# accra_A.net
KiCad netlist of a schematic drawn in EAGLE
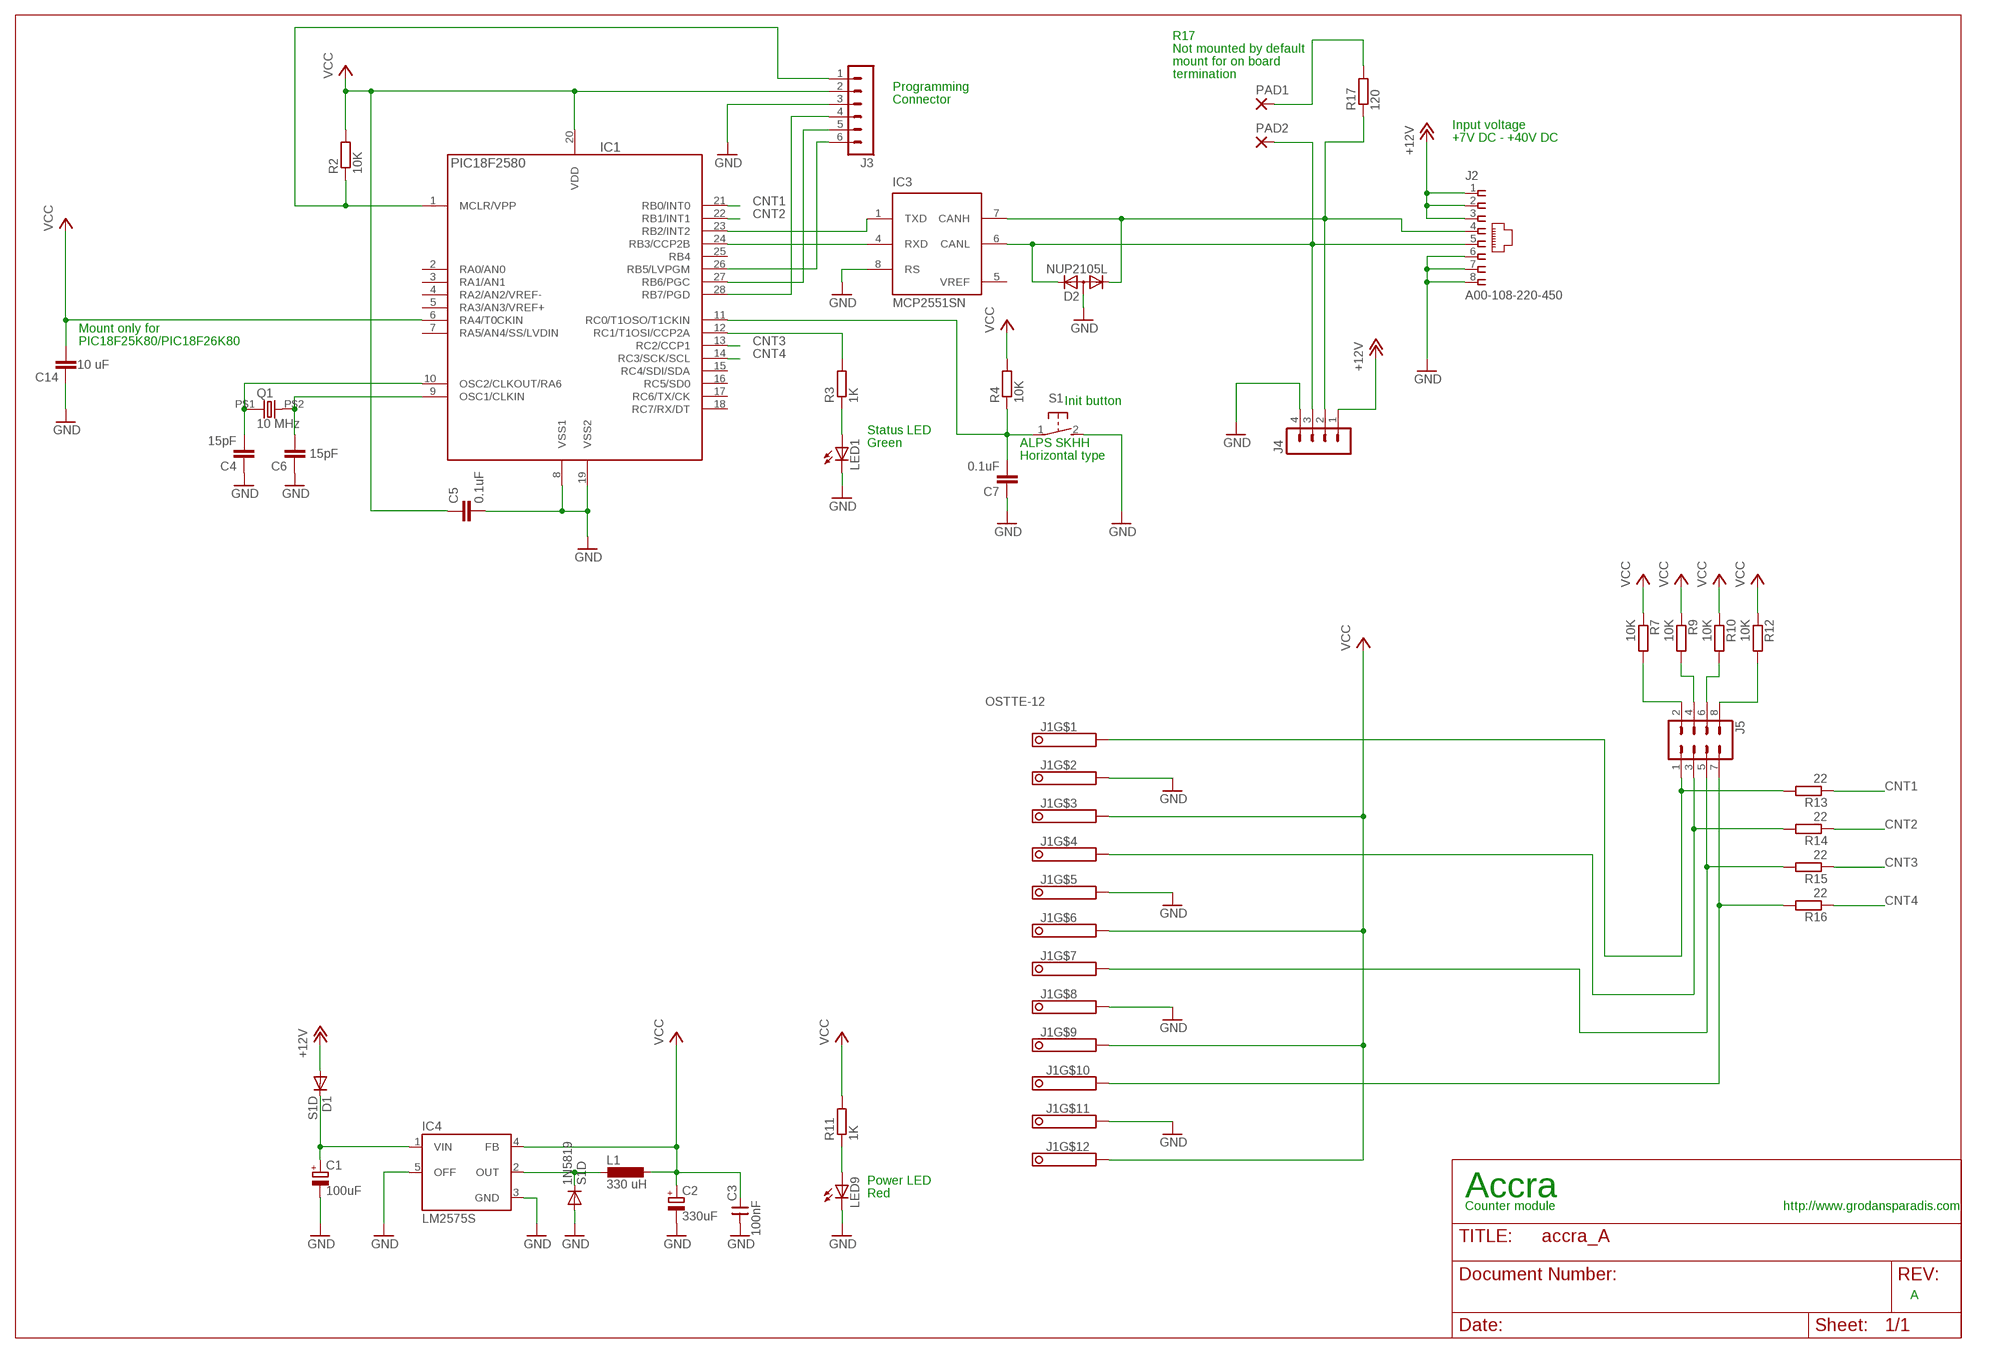
[diagram p0: schematic, sheet 1]

(export (version "E")
  (design (tool "Eeschema 10.0.6"))
  (components
    (comp (ref "1N5819")
      (value "S1D")
      (footprint "eagle-import:SOD123")
      (libsource (lib "eagle-import") (part "DIODE-SOD123"))
    )
    (comp (ref "C1")
      (value "100uF")
      (footprint "eagle-import:PANASONIC_D")
      (libsource (lib "eagle-import") (part "CPOL-EUD"))
    )
    (comp (ref "C2")
      (value "330uF")
      (footprint "eagle-import:PANASONIC_D")
      (libsource (lib "eagle-import") (part "CPOL-EUD"))
    )
    (comp (ref "C3")
      (value "100nF")
      (footprint "eagle-import:0805")
      (libsource (lib "eagle-import") (part "CNP-0805"))
    )
    (comp (ref "C4")
      (value "15pF")
      (footprint "eagle-import:C0805")
      (libsource (lib "eagle-import") (part "C-EUC0805"))
    )
    (comp (ref "C5")
      (value "0.1uF")
      (footprint "eagle-import:C0805")
      (libsource (lib "eagle-import") (part "C-EUC0805"))
    )
    (comp (ref "C6")
      (value "15pF")
      (footprint "eagle-import:C0805")
      (libsource (lib "eagle-import") (part "C-EUC0805"))
    )
    (comp (ref "C7")
      (value "0.1uF")
      (footprint "eagle-import:C0805")
      (libsource (lib "eagle-import") (part "C-EUC0805"))
    )
    (comp (ref "C14")
      (value "10 uF")
      (footprint "eagle-import:C0805")
      (libsource (lib "eagle-import") (part "C-EUC0805"))
    )
    (comp (ref "D1")
      (value "S1D")
      (footprint "eagle-import:SOD123")
      (libsource (lib "eagle-import") (part "DIODE-SOD123"))
    )
    (comp (ref "D2")
      (value "NUP2105L")
      (footprint "eagle-import:SOT23")
      (libsource (lib "eagle-import") (part "DIODE-2CA|ACSOT23"))
    )
    (comp (ref "IC1")
      (value "PIC18F2580")
      (footprint "eagle-import:SO28")
      (libsource (lib "eagle-import") (part "PIC18F252-?I/SOL"))
    )
    (comp (ref "IC3")
      (value "MCP2551SN")
      (footprint "eagle-import:SO-08")
      (libsource (lib "eagle-import") (part "MCP2551SN"))
    )
    (comp (ref "IC4")
      (value "LM2575S")
      (footprint "eagle-import:TO263-5")
      (libsource (lib "eagle-import") (part "LM2575S"))
    )
    (comp (ref "J1")
      (value "OSTTE-12")
      (footprint "eagle-import:PINHEAD-12")
      (libsource (lib "eagle-import") (part "OSTTE-12"))
    )
    (comp (ref "J2")
      (value "A00-108-220-450")
      (footprint "eagle-import:RJ-45")
      (libsource (lib "eagle-import") (part "A00-108-220-450"))
    )
    (comp (ref "J3")
      (value "MA06-1")
      (footprint "eagle-import:MA06-1")
      (libsource (lib "eagle-import") (part "MA06-1"))
    )
    (comp (ref "J4")
      (value "MA04-1")
      (footprint "eagle-import:MA04-1")
      (libsource (lib "eagle-import") (part "MA04-1"))
    )
    (comp (ref "J5")
      (value "MA04-2")
      (footprint "eagle-import:MA04-2")
      (libsource (lib "eagle-import") (part "MA04-2"))
    )
    (comp (ref "L1")
      (value "330 uH")
      (footprint "eagle-import:DO3316P")
      (libsource (lib "eagle-import") (part "DO3316P"))
    )
    (comp (ref "LED1")
      (value "LEDCHIP-LED0805")
      (footprint "eagle-import:CHIP-LED0805")
      (libsource (lib "eagle-import") (part "LEDCHIP-LED0805"))
    )
    (comp (ref "LED9")
      (value "LEDCHIP-LED0805")
      (footprint "eagle-import:CHIP-LED0805")
      (libsource (lib "eagle-import") (part "LEDCHIP-LED0805"))
    )
    (comp (ref "PAD1")
      (value "1,6/0,8")
      (footprint "eagle-import:1,6_0,8")
      (libsource (lib "eagle-import") (part "1,6/0,8"))
    )
    (comp (ref "PAD2")
      (value "1,6/0,8")
      (footprint "eagle-import:1,6_0,8")
      (libsource (lib "eagle-import") (part "1,6/0,8"))
    )
    (comp (ref "Q1")
      (value "10 MHz")
      (footprint "eagle-import:9C")
      (libsource (lib "eagle-import") (part "HC-49S"))
    )
    (comp (ref "R2")
      (value "10K")
      (footprint "eagle-import:R0805")
      (libsource (lib "eagle-import") (part "R-EU_R0805"))
    )
    (comp (ref "R3")
      (value "1K")
      (footprint "eagle-import:R0805")
      (libsource (lib "eagle-import") (part "R-EU_R0805"))
    )
    (comp (ref "R4")
      (value "10K")
      (footprint "eagle-import:R0805")
      (libsource (lib "eagle-import") (part "R-EU_R0805"))
    )
    (comp (ref "R7")
      (value "10K")
      (footprint "eagle-import:R0805")
      (libsource (lib "eagle-import") (part "R-EU_R0805"))
    )
    (comp (ref "R9")
      (value "10K")
      (footprint "eagle-import:R0805")
      (libsource (lib "eagle-import") (part "R-EU_R0805"))
    )
    (comp (ref "R10")
      (value "10K")
      (footprint "eagle-import:R0805")
      (libsource (lib "eagle-import") (part "R-EU_R0805"))
    )
    (comp (ref "R11")
      (value "1K")
      (footprint "eagle-import:R0805")
      (libsource (lib "eagle-import") (part "R-EU_R0805"))
    )
    (comp (ref "R12")
      (value "10K")
      (footprint "eagle-import:R0805")
      (libsource (lib "eagle-import") (part "R-EU_R0805"))
    )
    (comp (ref "R13")
      (value "22")
      (footprint "eagle-import:R0805")
      (libsource (lib "eagle-import") (part "R-EU_R0805"))
    )
    (comp (ref "R14")
      (value "22")
      (footprint "eagle-import:R0805")
      (libsource (lib "eagle-import") (part "R-EU_R0805"))
    )
    (comp (ref "R15")
      (value "22")
      (footprint "eagle-import:R0805")
      (libsource (lib "eagle-import") (part "R-EU_R0805"))
    )
    (comp (ref "R16")
      (value "22")
      (footprint "eagle-import:R0805")
      (libsource (lib "eagle-import") (part "R-EU_R0805"))
    )
    (comp (ref "R17")
      (value "120")
      (footprint "eagle-import:R0805")
      (libsource (lib "eagle-import") (part "R-EU_R0805"))
    )
    (comp (ref "S1")
      (value "31-XX")
      (footprint "eagle-import:B3F-31XX")
      (fields (field (name "MPN") "B3F-3100"))
      (libsource (lib "eagle-import") (part "31-XX"))
    )
  )
  (nets
    (net (code "1") (name "+12V") (class "Default")
      (node (ref "D1") (pin "A") (pinfunction "A_A") (pintype "passive"))
      (node (ref "J2") (pin "1") (pinfunction "1_1") (pintype "passive"))
      (node (ref "J2") (pin "2") (pinfunction "2_2") (pintype "passive"))
      (node (ref "J2") (pin "3") (pinfunction "3_3") (pintype "passive"))
      (node (ref "J4") (pin "1") (pinfunction "1_1") (pintype "passive"))
    )
    (net (code "2") (name "/CNT1") (class "Default")
      (node (ref "IC1") (pin "21") (pinfunction "RB0/INT0_21") (pintype "bidirectional"))
      (node (ref "R13") (pin "1") (pinfunction "1_1") (pintype "passive"))
    )
    (net (code "3") (name "/CNT2") (class "Default")
      (node (ref "IC1") (pin "22") (pinfunction "RB1/INT1_22") (pintype "bidirectional"))
      (node (ref "R14") (pin "1") (pinfunction "1_1") (pintype "passive"))
    )
    (net (code "4") (name "/CNT3") (class "Default")
      (node (ref "IC1") (pin "13") (pinfunction "RC2/CCP1_13") (pintype "bidirectional"))
      (node (ref "R15") (pin "1") (pinfunction "1_1") (pintype "passive"))
    )
    (net (code "5") (name "/CNT4") (class "Default")
      (node (ref "IC1") (pin "14") (pinfunction "RC3/SCK/SCL_14") (pintype "bidirectional"))
      (node (ref "R16") (pin "1") (pinfunction "1_1") (pintype "passive"))
    )
    (net (code "6") (name "/VREF") (class "Default")
      (node (ref "IC3") (pin "5") (pinfunction "VREF_5") (pintype "power_in"))
    )
    (net (code "7") (name "GND") (class "Default")
      (node (ref "1N5819") (pin "A") (pinfunction "A_A") (pintype "passive"))
      (node (ref "C1") (pin "-") (pinfunction "-_-") (pintype "passive"))
      (node (ref "C14") (pin "1") (pinfunction "1_1") (pintype "passive"))
      (node (ref "C2") (pin "-") (pinfunction "-_-") (pintype "passive"))
      (node (ref "C3") (pin "1") (pinfunction "1_1") (pintype "passive"))
      (node (ref "C4") (pin "1") (pinfunction "1_1") (pintype "passive"))
      (node (ref "C5") (pin "2") (pinfunction "2_2") (pintype "passive"))
      (node (ref "C6") (pin "1") (pinfunction "1_1") (pintype "passive"))
      (node (ref "C7") (pin "1") (pinfunction "1_1") (pintype "passive"))
      (node (ref "D2") (pin "3") (pinfunction "A_3") (pintype "passive"))
      (node (ref "IC1") (pin "19") (pinfunction "VSS2_19") (pintype "power_in"))
      (node (ref "IC1") (pin "8") (pinfunction "VSS1_8") (pintype "power_in"))
      (node (ref "IC3") (pin "8") (pinfunction "RS_8") (pintype "input"))
      (node (ref "IC4") (pin "3") (pinfunction "GND_3") (pintype "power_in"))
      (node (ref "IC4") (pin "5") (pinfunction "OFF_5") (pintype "input"))
      (node (ref "J1") (pin "11") (pinfunction "K_11") (pintype "passive"))
      (node (ref "J1") (pin "2") (pinfunction "K_2") (pintype "passive"))
      (node (ref "J1") (pin "5") (pinfunction "K_5") (pintype "passive"))
      (node (ref "J1") (pin "8") (pinfunction "K_8") (pintype "passive"))
      (node (ref "J2") (pin "6") (pinfunction "6_6") (pintype "passive"))
      (node (ref "J2") (pin "7") (pinfunction "7_7") (pintype "passive"))
      (node (ref "J2") (pin "8") (pinfunction "8_8") (pintype "passive"))
      (node (ref "J3") (pin "3") (pinfunction "3_3") (pintype "passive"))
      (node (ref "J4") (pin "4") (pinfunction "4_4") (pintype "passive"))
      (node (ref "LED1") (pin "C") (pinfunction "C_C") (pintype "passive"))
      (node (ref "LED9") (pin "C") (pinfunction "C_C") (pintype "passive"))
      (node (ref "S1") (pin "2") (pinfunction "S_2") (pintype "passive"))
    )
    (net (code "8") (name "Net-(D2-K1)") (class "Default")
      (node (ref "D2") (pin "1") (pinfunction "K1_1") (pintype "passive"))
      (node (ref "IC3") (pin "7") (pinfunction "CANH_7") (pintype "bidirectional"))
      (node (ref "J2") (pin "4") (pinfunction "4_4") (pintype "passive"))
      (node (ref "J4") (pin "2") (pinfunction "2_2") (pintype "passive"))
      (node (ref "R17") (pin "1") (pinfunction "1_1") (pintype "passive"))
    )
    (net (code "9") (name "Net-(D2-K2)") (class "Default")
      (node (ref "D2") (pin "2") (pinfunction "K2_2") (pintype "passive"))
      (node (ref "IC3") (pin "6") (pinfunction "CANL_6") (pintype "bidirectional"))
      (node (ref "J2") (pin "5") (pinfunction "5_5") (pintype "passive"))
      (node (ref "J4") (pin "3") (pinfunction "3_3") (pintype "passive"))
      (node (ref "PAD2") (pin "1") (pinfunction "P_1") (pintype "passive"))
    )
    (net (code "10") (name "Net-(IC1-MCLR{slash}VPP)") (class "Default")
      (node (ref "IC1") (pin "1") (pinfunction "MCLR/VPP_1") (pintype "input"))
      (node (ref "J3") (pin "1") (pinfunction "1_1") (pintype "passive"))
      (node (ref "R2") (pin "1") (pinfunction "1_1") (pintype "passive"))
    )
    (net (code "11") (name "Net-(IC1-OSC1{slash}CLKIN)") (class "Default")
      (node (ref "C6") (pin "2") (pinfunction "2_2") (pintype "passive"))
      (node (ref "IC1") (pin "9") (pinfunction "OSC1/CLKIN_9") (pintype "input"))
      (node (ref "Q1") (pin "P$2") (pinfunction "2_P$2") (pintype "passive"))
    )
    (net (code "12") (name "Net-(IC1-OSC2{slash}CLKOUT{slash}RA6)") (class "Default")
      (node (ref "C4") (pin "2") (pinfunction "2_2") (pintype "passive"))
      (node (ref "IC1") (pin "10") (pinfunction "OSC2/CLKOUT/RA6_10") (pintype "output"))
      (node (ref "Q1") (pin "P$1") (pinfunction "1_P$1") (pintype "passive"))
    )
    (net (code "13") (name "Net-(IC1-RB2{slash}INT2)") (class "Default")
      (node (ref "IC1") (pin "23") (pinfunction "RB2/INT2_23") (pintype "bidirectional"))
      (node (ref "IC3") (pin "1") (pinfunction "TXD_1") (pintype "input"))
    )
    (net (code "14") (name "Net-(IC1-RB3{slash}CCP2B)") (class "Default")
      (node (ref "IC1") (pin "24") (pinfunction "RB3/CCP2B_24") (pintype "bidirectional"))
      (node (ref "IC3") (pin "4") (pinfunction "RXD_4") (pintype "output"))
    )
    (net (code "15") (name "Net-(IC1-RB5{slash}LVPGM)") (class "Default")
      (node (ref "IC1") (pin "26") (pinfunction "RB5/LVPGM_26") (pintype "bidirectional"))
      (node (ref "J3") (pin "6") (pinfunction "6_6") (pintype "passive"))
    )
    (net (code "16") (name "Net-(IC1-RB6{slash}PGC)") (class "Default")
      (node (ref "IC1") (pin "27") (pinfunction "RB6/PGC_27") (pintype "bidirectional"))
      (node (ref "J3") (pin "5") (pinfunction "5_5") (pintype "passive"))
    )
    (net (code "17") (name "Net-(IC1-RB7{slash}PGD)") (class "Default")
      (node (ref "IC1") (pin "28") (pinfunction "RB7/PGD_28") (pintype "bidirectional"))
      (node (ref "J3") (pin "4") (pinfunction "4_4") (pintype "passive"))
    )
    (net (code "18") (name "Net-(IC1-RC0{slash}T1OSO{slash}T1CKIN)") (class "Default")
      (node (ref "C7") (pin "2") (pinfunction "2_2") (pintype "passive"))
      (node (ref "IC1") (pin "11") (pinfunction "RC0/T1OSO/T1CKIN_11") (pintype "bidirectional"))
      (node (ref "R4") (pin "1") (pinfunction "1_1") (pintype "passive"))
      (node (ref "S1") (pin "1") (pinfunction "P_1") (pintype "passive"))
    )
    (net (code "19") (name "Net-(IC1-RC1{slash}T1OSI{slash}CCP2A)") (class "Default")
      (node (ref "IC1") (pin "12") (pinfunction "RC1/T1OSI/CCP2A_12") (pintype "bidirectional"))
      (node (ref "R3") (pin "2") (pinfunction "2_2") (pintype "passive"))
    )
    (net (code "20") (name "Net-(IC4-OUT)") (class "Default")
      (node (ref "1N5819") (pin "C") (pinfunction "C_C") (pintype "passive"))
      (node (ref "IC4") (pin "2") (pinfunction "OUT_2") (pintype "output"))
      (node (ref "L1") (pin "1") (pinfunction "1_1") (pintype "passive"))
    )
    (net (code "21") (name "Net-(IC4-VIN)") (class "Default")
      (node (ref "C1") (pin "+") (pinfunction "+_+") (pintype "passive"))
      (node (ref "D1") (pin "C") (pinfunction "C_C") (pintype "passive"))
      (node (ref "IC4") (pin "1") (pinfunction "VIN_1") (pintype "power_in"))
    )
    (net (code "22") (name "Net-(J1A-K)") (class "Default")
      (node (ref "J1") (pin "1") (pinfunction "K_1") (pintype "passive"))
      (node (ref "J5") (pin "1") (pinfunction "1_1") (pintype "passive"))
      (node (ref "R13") (pin "2") (pinfunction "2_2") (pintype "passive"))
    )
    (net (code "23") (name "Net-(J1B-K)") (class "Default")
      (node (ref "J1") (pin "10") (pinfunction "K_10") (pintype "passive"))
      (node (ref "J5") (pin "7") (pinfunction "7_7") (pintype "passive"))
      (node (ref "R16") (pin "2") (pinfunction "2_2") (pintype "passive"))
    )
    (net (code "24") (name "Net-(J1G-K)") (class "Default")
      (node (ref "J1") (pin "4") (pinfunction "K_4") (pintype "passive"))
      (node (ref "J5") (pin "3") (pinfunction "3_3") (pintype "passive"))
      (node (ref "R14") (pin "2") (pinfunction "2_2") (pintype "passive"))
    )
    (net (code "25") (name "Net-(J1J-K)") (class "Default")
      (node (ref "J1") (pin "7") (pinfunction "K_7") (pintype "passive"))
      (node (ref "J5") (pin "5") (pinfunction "5_5") (pintype "passive"))
      (node (ref "R15") (pin "2") (pinfunction "2_2") (pintype "passive"))
    )
    (net (code "26") (name "Net-(J5-Pad2)") (class "Default")
      (node (ref "J5") (pin "2") (pinfunction "2_2") (pintype "passive"))
      (node (ref "R7") (pin "2") (pinfunction "2_2") (pintype "passive"))
    )
    (net (code "27") (name "Net-(J5-Pad4)") (class "Default")
      (node (ref "J5") (pin "4") (pinfunction "4_4") (pintype "passive"))
      (node (ref "R9") (pin "2") (pinfunction "2_2") (pintype "passive"))
    )
    (net (code "28") (name "Net-(J5-Pad6)") (class "Default")
      (node (ref "J5") (pin "6") (pinfunction "6_6") (pintype "passive"))
      (node (ref "R10") (pin "2") (pinfunction "2_2") (pintype "passive"))
    )
    (net (code "29") (name "Net-(J5-Pad8)") (class "Default")
      (node (ref "J5") (pin "8") (pinfunction "8_8") (pintype "passive"))
      (node (ref "R12") (pin "2") (pinfunction "2_2") (pintype "passive"))
    )
    (net (code "30") (name "Net-(LED1-PadA)") (class "Default")
      (node (ref "LED1") (pin "A") (pinfunction "A_A") (pintype "passive"))
      (node (ref "R3") (pin "1") (pinfunction "1_1") (pintype "passive"))
    )
    (net (code "31") (name "Net-(LED9-PadA)") (class "Default")
      (node (ref "LED9") (pin "A") (pinfunction "A_A") (pintype "passive"))
      (node (ref "R11") (pin "1") (pinfunction "1_1") (pintype "passive"))
    )
    (net (code "32") (name "Net-(PAD1-P)") (class "Default")
      (node (ref "PAD1") (pin "1") (pinfunction "P_1") (pintype "passive"))
      (node (ref "R17") (pin "2") (pinfunction "2_2") (pintype "passive"))
    )
    (net (code "33") (name "VCC") (class "Default")
      (node (ref "C14") (pin "2") (pinfunction "2_2") (pintype "passive"))
      (node (ref "C2") (pin "+") (pinfunction "+_+") (pintype "passive"))
      (node (ref "C3") (pin "2") (pinfunction "2_2") (pintype "passive"))
      (node (ref "C5") (pin "1") (pinfunction "1_1") (pintype "passive"))
      (node (ref "IC1") (pin "20") (pinfunction "VDD_20") (pintype "power_in"))
      (node (ref "IC1") (pin "6") (pinfunction "RA4/T0CKIN_6") (pintype "open_collector"))
      (node (ref "IC4") (pin "4") (pinfunction "FB_4") (pintype "input"))
      (node (ref "J1") (pin "12") (pinfunction "K_12") (pintype "passive"))
      (node (ref "J1") (pin "3") (pinfunction "K_3") (pintype "passive"))
      (node (ref "J1") (pin "6") (pinfunction "K_6") (pintype "passive"))
      (node (ref "J1") (pin "9") (pinfunction "K_9") (pintype "passive"))
      (node (ref "J3") (pin "2") (pinfunction "2_2") (pintype "passive"))
      (node (ref "L1") (pin "2") (pinfunction "2_2") (pintype "passive"))
      (node (ref "R10") (pin "1") (pinfunction "1_1") (pintype "passive"))
      (node (ref "R11") (pin "2") (pinfunction "2_2") (pintype "passive"))
      (node (ref "R12") (pin "1") (pinfunction "1_1") (pintype "passive"))
      (node (ref "R2") (pin "2") (pinfunction "2_2") (pintype "passive"))
      (node (ref "R4") (pin "2") (pinfunction "2_2") (pintype "passive"))
      (node (ref "R7") (pin "1") (pinfunction "1_1") (pintype "passive"))
      (node (ref "R9") (pin "1") (pinfunction "1_1") (pintype "passive"))
    )
    (net (code "34") (name "unconnected-(IC1-RA0{slash}AN0-Pad2)") (class "Default")
      (node (ref "IC1") (pin "2") (pinfunction "RA0/AN0_2") (pintype "bidirectional"))
    )
    (net (code "35") (name "unconnected-(IC1-RA1{slash}AN1-Pad3)") (class "Default")
      (node (ref "IC1") (pin "3") (pinfunction "RA1/AN1_3") (pintype "bidirectional"))
    )
    (net (code "36") (name "unconnected-(IC1-RA2{slash}AN2{slash}VREF--Pad4)") (class "Default")
      (node (ref "IC1") (pin "4") (pinfunction "RA2/AN2/VREF-_4") (pintype "bidirectional"))
    )
    (net (code "37") (name "unconnected-(IC1-RA3{slash}AN3{slash}VREF+-Pad5)") (class "Default")
      (node (ref "IC1") (pin "5") (pinfunction "RA3/AN3/VREF+_5") (pintype "bidirectional"))
    )
    (net (code "38") (name "unconnected-(IC1-RA5{slash}AN4{slash}SS{slash}LVDIN-Pad7)") (class "Default")
      (node (ref "IC1") (pin "7") (pinfunction "RA5/AN4/SS/LVDIN_7") (pintype "bidirectional"))
    )
    (net (code "39") (name "unconnected-(IC1-RB4-Pad25)") (class "Default")
      (node (ref "IC1") (pin "25") (pinfunction "RB4_25") (pintype "bidirectional"))
    )
    (net (code "40") (name "unconnected-(IC1-RC4{slash}SDI{slash}SDA-Pad15)") (class "Default")
      (node (ref "IC1") (pin "15") (pinfunction "RC4/SDI/SDA_15") (pintype "bidirectional"))
    )
    (net (code "41") (name "unconnected-(IC1-RC5{slash}SD0-Pad16)") (class "Default")
      (node (ref "IC1") (pin "16") (pinfunction "RC5/SD0_16") (pintype "bidirectional"))
    )
    (net (code "42") (name "unconnected-(IC1-RC6{slash}TX{slash}CK-Pad17)") (class "Default")
      (node (ref "IC1") (pin "17") (pinfunction "RC6/TX/CK_17") (pintype "bidirectional"))
    )
    (net (code "43") (name "unconnected-(IC1-RC7{slash}RX{slash}DT-Pad18)") (class "Default")
      (node (ref "IC1") (pin "18") (pinfunction "RC7/RX/DT_18") (pintype "bidirectional"))
    )
  )
)
